# svf.net
KiCad netlist of a schematic drawn in EAGLE
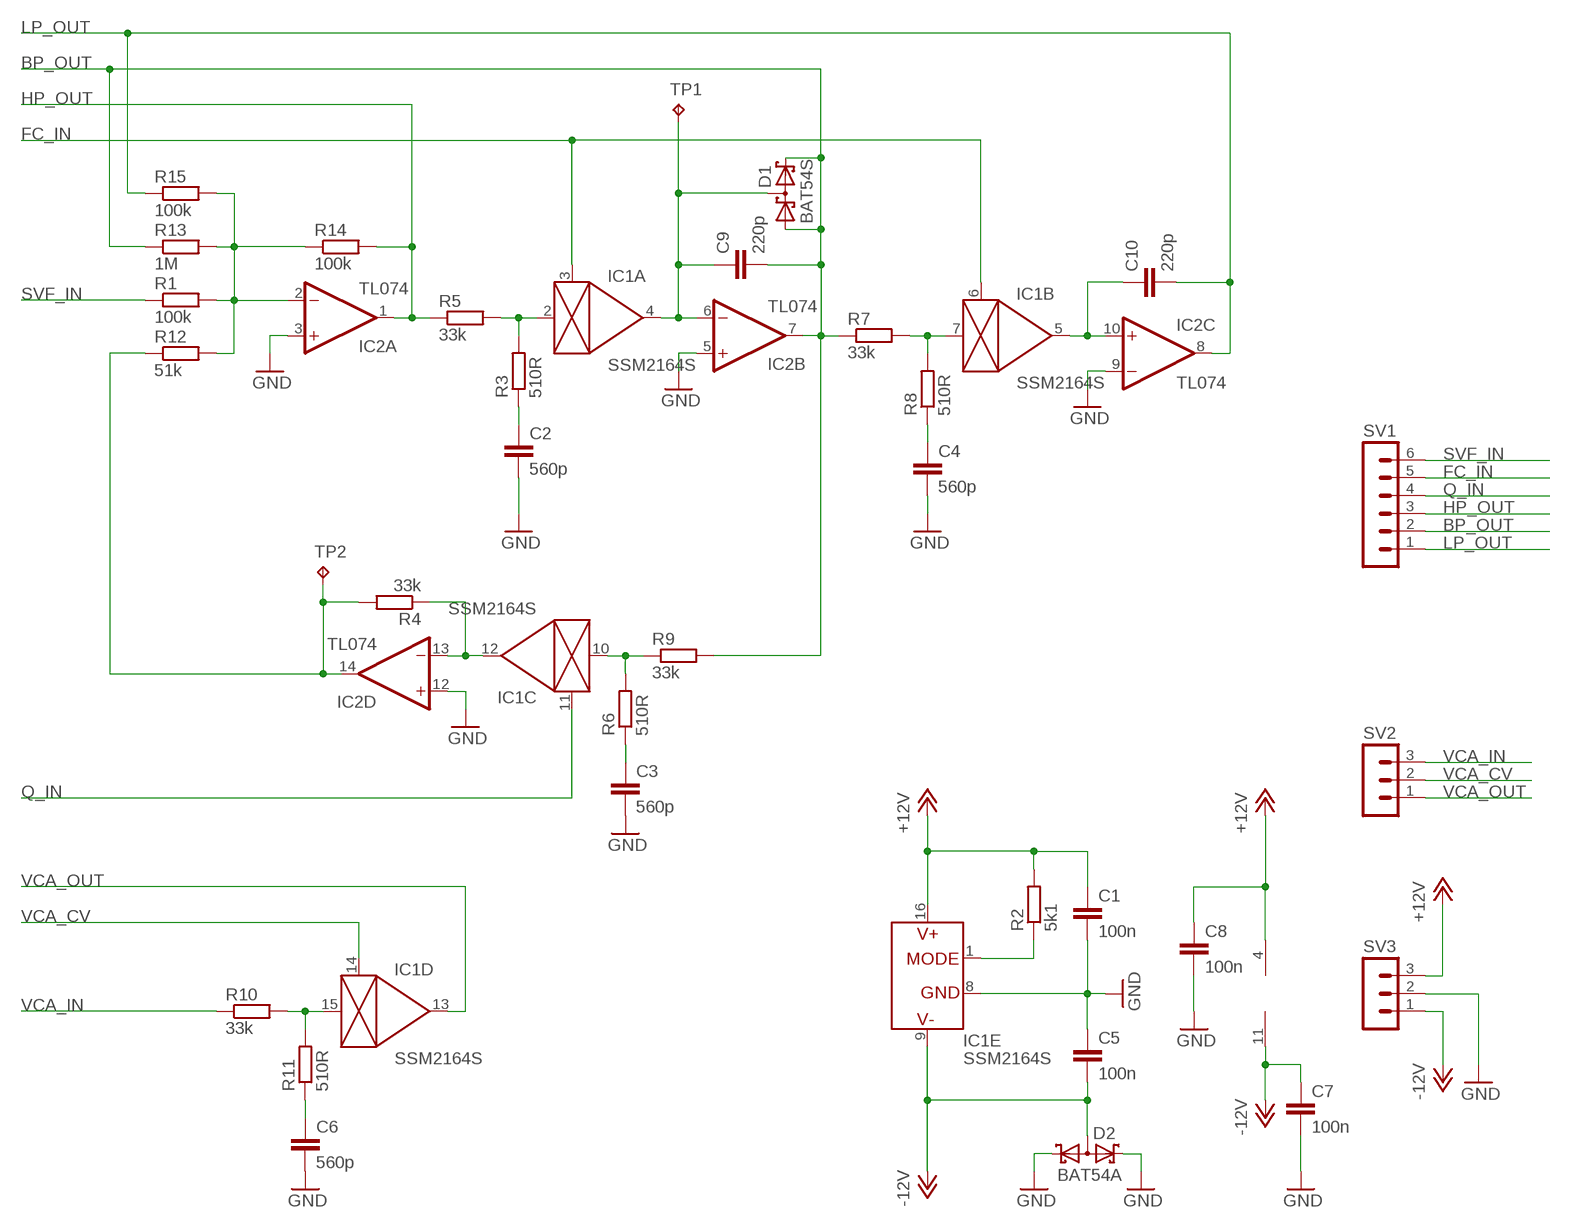
[diagram p0: schematic, sheet 1]

(export (version "E")
  (design (tool "Eeschema 10.0.6"))
  (components
    (comp (ref "C1")
      (value "100n")
      (footprint "eagle-import:C0603")
      (libsource (lib "eagle-import") (part "C-EUC0603"))
    )
    (comp (ref "C2")
      (value "560p")
      (footprint "eagle-import:C0603")
      (libsource (lib "eagle-import") (part "C-EUC0603"))
    )
    (comp (ref "C3")
      (value "560p")
      (footprint "eagle-import:C0603")
      (libsource (lib "eagle-import") (part "C-EUC0603"))
    )
    (comp (ref "C4")
      (value "560p")
      (footprint "eagle-import:C0603")
      (libsource (lib "eagle-import") (part "C-EUC0603"))
    )
    (comp (ref "C5")
      (value "100n")
      (footprint "eagle-import:C0603")
      (libsource (lib "eagle-import") (part "C-EUC0603"))
    )
    (comp (ref "C6")
      (value "560p")
      (footprint "eagle-import:C0603")
      (libsource (lib "eagle-import") (part "C-EUC0603"))
    )
    (comp (ref "C7")
      (value "100n")
      (footprint "eagle-import:C0603")
      (libsource (lib "eagle-import") (part "C-EUC0603"))
    )
    (comp (ref "C8")
      (value "100n")
      (footprint "eagle-import:C0603")
      (libsource (lib "eagle-import") (part "C-EUC0603"))
    )
    (comp (ref "C9")
      (value "220p")
      (footprint "eagle-import:C0603")
      (libsource (lib "eagle-import") (part "C-EUC0603"))
    )
    (comp (ref "C10")
      (value "220p")
      (footprint "eagle-import:C0603")
      (libsource (lib "eagle-import") (part "C-EUC0603"))
    )
    (comp (ref "D1")
      (value "BAT54S")
      (footprint "eagle-import:SOT23")
      (libsource (lib "eagle-import") (part "BAT54S"))
    )
    (comp (ref "D2")
      (value "BAT54A")
      (footprint "eagle-import:SOT23")
      (libsource (lib "eagle-import") (part "BAT54A"))
    )
    (comp (ref "IC1")
      (value "SSM2164S")
      (footprint "eagle-import:SOIC16N")
      (libsource (lib "eagle-import") (part "SSM2164S"))
    )
    (comp (ref "IC2")
      (value "TL074")
      (footprint "eagle-import:SO14")
      (libsource (lib "eagle-import") (part "TL074D"))
    )
    (comp (ref "R1")
      (value "100k")
      (footprint "eagle-import:0603")
      (libsource (lib "eagle-import") (part "R-EU_0603"))
    )
    (comp (ref "R2")
      (value "5k1")
      (footprint "eagle-import:0603")
      (libsource (lib "eagle-import") (part "R-EU_0603"))
    )
    (comp (ref "R3")
      (value "510R")
      (footprint "eagle-import:0603")
      (libsource (lib "eagle-import") (part "R-EU_0603"))
    )
    (comp (ref "R4")
      (value "33k")
      (footprint "eagle-import:0603")
      (libsource (lib "eagle-import") (part "R-EU_0603"))
    )
    (comp (ref "R5")
      (value "33k")
      (footprint "eagle-import:0603")
      (libsource (lib "eagle-import") (part "R-EU_0603"))
    )
    (comp (ref "R6")
      (value "510R")
      (footprint "eagle-import:0603")
      (libsource (lib "eagle-import") (part "R-EU_0603"))
    )
    (comp (ref "R7")
      (value "33k")
      (footprint "eagle-import:0603")
      (libsource (lib "eagle-import") (part "R-EU_0603"))
    )
    (comp (ref "R8")
      (value "510R")
      (footprint "eagle-import:0603")
      (libsource (lib "eagle-import") (part "R-EU_0603"))
    )
    (comp (ref "R9")
      (value "33k")
      (footprint "eagle-import:0603")
      (libsource (lib "eagle-import") (part "R-EU_0603"))
    )
    (comp (ref "R10")
      (value "33k")
      (footprint "eagle-import:0603")
      (libsource (lib "eagle-import") (part "R-EU_0603"))
    )
    (comp (ref "R11")
      (value "510R")
      (footprint "eagle-import:0603")
      (libsource (lib "eagle-import") (part "R-EU_0603"))
    )
    (comp (ref "R12")
      (value "51k")
      (footprint "eagle-import:0603")
      (libsource (lib "eagle-import") (part "R-EU_0603"))
    )
    (comp (ref "R13")
      (value "1M")
      (footprint "eagle-import:0603")
      (libsource (lib "eagle-import") (part "R-EU_0603"))
    )
    (comp (ref "R14")
      (value "100k")
      (footprint "eagle-import:0603")
      (libsource (lib "eagle-import") (part "R-EU_0603"))
    )
    (comp (ref "R15")
      (value "100k")
      (footprint "eagle-import:0603")
      (libsource (lib "eagle-import") (part "R-EU_0603"))
    )
    (comp (ref "SV1")
      (value "MA06-1")
      (footprint "eagle-import:MA06-1")
      (libsource (lib "eagle-import") (part "MA06-1"))
    )
    (comp (ref "SV2")
      (value "MA03-1")
      (footprint "eagle-import:MA03-1")
      (libsource (lib "eagle-import") (part "MA03-1"))
    )
    (comp (ref "SV3")
      (value "MA03-1")
      (footprint "eagle-import:MA03-1")
      (libsource (lib "eagle-import") (part "MA03-1"))
    )
    (comp (ref "TP1")
      (value "TPPAD1-13")
      (footprint "eagle-import:P1-13")
      (libsource (lib "eagle-import") (part "TPPAD1-13"))
    )
    (comp (ref "TP2")
      (value "TPPAD1-13")
      (footprint "eagle-import:P1-13")
      (libsource (lib "eagle-import") (part "TPPAD1-13"))
    )
  )
  (nets
    (net (code "1") (name "+12V") (class "Default")
      (node (ref "C1") (pin "1") (pinfunction "1_1") (pintype "passive"))
      (node (ref "C8") (pin "1") (pinfunction "1_1") (pintype "passive"))
      (node (ref "IC1") (pin "16") (pinfunction "V+_16") (pintype "power_in"))
      (node (ref "IC2") (pin "4") (pinfunction "V+_4") (pintype "power_in"))
      (node (ref "R2") (pin "2") (pinfunction "2_2") (pintype "passive"))
      (node (ref "SV3") (pin "3") (pinfunction "3_3") (pintype "passive"))
    )
    (net (code "2") (name "-12V") (class "Default")
      (node (ref "C5") (pin "2") (pinfunction "2_2") (pintype "passive"))
      (node (ref "C7") (pin "1") (pinfunction "1_1") (pintype "passive"))
      (node (ref "D2") (pin "3") (pinfunction "AA_3") (pintype "passive"))
      (node (ref "IC1") (pin "9") (pinfunction "V-_9") (pintype "power_in"))
      (node (ref "IC2") (pin "11") (pinfunction "V-_11") (pintype "power_in"))
      (node (ref "SV3") (pin "1") (pinfunction "1_1") (pintype "passive"))
    )
    (net (code "3") (name "/BP_OUT") (class "Default")
      (node (ref "C9") (pin "2") (pinfunction "2_2") (pintype "passive"))
      (node (ref "D1") (pin "1") (pinfunction "A1_1") (pintype "passive"))
      (node (ref "D1") (pin "2") (pinfunction "C2_2") (pintype "passive"))
      (node (ref "IC2") (pin "7") (pinfunction "OUT_7") (pintype "output"))
      (node (ref "R13") (pin "1") (pinfunction "1_1") (pintype "passive"))
      (node (ref "R7") (pin "1") (pinfunction "1_1") (pintype "passive"))
      (node (ref "R9") (pin "2") (pinfunction "2_2") (pintype "passive"))
      (node (ref "SV1") (pin "2") (pinfunction "2_2") (pintype "passive"))
    )
    (net (code "4") (name "/FC_IN") (class "Default")
      (node (ref "IC1") (pin "3") (pinfunction "CTRL_3") (pintype "input"))
      (node (ref "IC1") (pin "6") (pinfunction "CTRL_6") (pintype "input"))
      (node (ref "SV1") (pin "5") (pinfunction "5_5") (pintype "passive"))
    )
    (net (code "5") (name "/HP_OUT") (class "Default")
      (node (ref "IC2") (pin "1") (pinfunction "OUT_1") (pintype "output"))
      (node (ref "R14") (pin "2") (pinfunction "2_2") (pintype "passive"))
      (node (ref "R5") (pin "1") (pinfunction "1_1") (pintype "passive"))
      (node (ref "SV1") (pin "3") (pinfunction "3_3") (pintype "passive"))
    )
    (net (code "6") (name "/LP_OUT") (class "Default")
      (node (ref "C10") (pin "2") (pinfunction "2_2") (pintype "passive"))
      (node (ref "IC2") (pin "8") (pinfunction "OUT_8") (pintype "output"))
      (node (ref "R15") (pin "1") (pinfunction "1_1") (pintype "passive"))
      (node (ref "SV1") (pin "1") (pinfunction "1_1") (pintype "passive"))
    )
    (net (code "7") (name "/Q_IN") (class "Default")
      (node (ref "IC1") (pin "11") (pinfunction "CTRL_11") (pintype "input"))
      (node (ref "SV1") (pin "4") (pinfunction "4_4") (pintype "passive"))
    )
    (net (code "8") (name "/SVF_IN") (class "Default")
      (node (ref "R1") (pin "1") (pinfunction "1_1") (pintype "passive"))
      (node (ref "SV1") (pin "6") (pinfunction "6_6") (pintype "passive"))
    )
    (net (code "9") (name "/VCA_CV") (class "Default")
      (node (ref "IC1") (pin "14") (pinfunction "CTRL_14") (pintype "input"))
      (node (ref "SV2") (pin "2") (pinfunction "2_2") (pintype "passive"))
    )
    (net (code "10") (name "/VCA_IN") (class "Default")
      (node (ref "R10") (pin "1") (pinfunction "1_1") (pintype "passive"))
      (node (ref "SV2") (pin "3") (pinfunction "3_3") (pintype "passive"))
    )
    (net (code "11") (name "/VCA_OUT") (class "Default")
      (node (ref "IC1") (pin "13") (pinfunction "OUT_13") (pintype "output"))
      (node (ref "SV2") (pin "1") (pinfunction "1_1") (pintype "passive"))
    )
    (net (code "12") (name "GND") (class "Default")
      (node (ref "C1") (pin "2") (pinfunction "2_2") (pintype "passive"))
      (node (ref "C2") (pin "2") (pinfunction "2_2") (pintype "passive"))
      (node (ref "C3") (pin "2") (pinfunction "2_2") (pintype "passive"))
      (node (ref "C4") (pin "2") (pinfunction "2_2") (pintype "passive"))
      (node (ref "C5") (pin "1") (pinfunction "1_1") (pintype "passive"))
      (node (ref "C6") (pin "2") (pinfunction "2_2") (pintype "passive"))
      (node (ref "C7") (pin "2") (pinfunction "2_2") (pintype "passive"))
      (node (ref "C8") (pin "2") (pinfunction "2_2") (pintype "passive"))
      (node (ref "D2") (pin "1") (pinfunction "K1_1") (pintype "passive"))
      (node (ref "D2") (pin "2") (pinfunction "K2_2") (pintype "passive"))
      (node (ref "IC1") (pin "8") (pinfunction "GND_8") (pintype "power_in"))
      (node (ref "IC2") (pin "12") (pinfunction "+IN_12") (pintype "input"))
      (node (ref "IC2") (pin "3") (pinfunction "+IN_3") (pintype "input"))
      (node (ref "IC2") (pin "5") (pinfunction "+IN_5") (pintype "input"))
      (node (ref "IC2") (pin "9") (pinfunction "-IN_9") (pintype "input"))
      (node (ref "SV3") (pin "2") (pinfunction "2_2") (pintype "passive"))
    )
    (net (code "13") (name "Net-(C2-Pad1)") (class "Default")
      (node (ref "C2") (pin "1") (pinfunction "1_1") (pintype "passive"))
      (node (ref "R3") (pin "1") (pinfunction "1_1") (pintype "passive"))
    )
    (net (code "14") (name "Net-(C3-Pad1)") (class "Default")
      (node (ref "C3") (pin "1") (pinfunction "1_1") (pintype "passive"))
      (node (ref "R6") (pin "1") (pinfunction "1_1") (pintype "passive"))
    )
    (net (code "15") (name "Net-(C4-Pad1)") (class "Default")
      (node (ref "C4") (pin "1") (pinfunction "1_1") (pintype "passive"))
      (node (ref "R8") (pin "1") (pinfunction "1_1") (pintype "passive"))
    )
    (net (code "16") (name "Net-(C6-Pad1)") (class "Default")
      (node (ref "C6") (pin "1") (pinfunction "1_1") (pintype "passive"))
      (node (ref "R11") (pin "1") (pinfunction "1_1") (pintype "passive"))
    )
    (net (code "17") (name "Net-(D1-C1A2)") (class "Default")
      (node (ref "C9") (pin "1") (pinfunction "1_1") (pintype "passive"))
      (node (ref "D1") (pin "3") (pinfunction "C1A2_3") (pintype "passive"))
      (node (ref "IC1") (pin "4") (pinfunction "OUT_4") (pintype "output"))
      (node (ref "IC2") (pin "6") (pinfunction "-IN_6") (pintype "input"))
      (node (ref "TP1") (pin "TP") (pinfunction "TP_TP") (pintype "input"))
    )
    (net (code "18") (name "Net-(IC1A-IN)") (class "Default")
      (node (ref "IC1") (pin "2") (pinfunction "IN_2") (pintype "input"))
      (node (ref "R3") (pin "2") (pinfunction "2_2") (pintype "passive"))
      (node (ref "R5") (pin "2") (pinfunction "2_2") (pintype "passive"))
    )
    (net (code "19") (name "Net-(IC1B-IN)") (class "Default")
      (node (ref "IC1") (pin "7") (pinfunction "IN_7") (pintype "input"))
      (node (ref "R7") (pin "2") (pinfunction "2_2") (pintype "passive"))
      (node (ref "R8") (pin "2") (pinfunction "2_2") (pintype "passive"))
    )
    (net (code "20") (name "Net-(IC1B-OUT)") (class "Default")
      (node (ref "C10") (pin "1") (pinfunction "1_1") (pintype "passive"))
      (node (ref "IC1") (pin "5") (pinfunction "OUT_5") (pintype "output"))
      (node (ref "IC2") (pin "10") (pinfunction "+IN_10") (pintype "input"))
    )
    (net (code "21") (name "Net-(IC1C-IN)") (class "Default")
      (node (ref "IC1") (pin "10") (pinfunction "IN_10") (pintype "input"))
      (node (ref "R6") (pin "2") (pinfunction "2_2") (pintype "passive"))
      (node (ref "R9") (pin "1") (pinfunction "1_1") (pintype "passive"))
    )
    (net (code "22") (name "Net-(IC1C-OUT)") (class "Default")
      (node (ref "IC1") (pin "12") (pinfunction "OUT_12") (pintype "output"))
      (node (ref "IC2") (pin "13") (pinfunction "-IN_13") (pintype "input"))
      (node (ref "R4") (pin "1") (pinfunction "1_1") (pintype "passive"))
    )
    (net (code "23") (name "Net-(IC1D-IN)") (class "Default")
      (node (ref "IC1") (pin "15") (pinfunction "IN_15") (pintype "input"))
      (node (ref "R10") (pin "2") (pinfunction "2_2") (pintype "passive"))
      (node (ref "R11") (pin "2") (pinfunction "2_2") (pintype "passive"))
    )
    (net (code "24") (name "Net-(IC1E-MODE)") (class "Default")
      (node (ref "IC1") (pin "1") (pinfunction "MODE_1") (pintype "input"))
      (node (ref "R2") (pin "1") (pinfunction "1_1") (pintype "passive"))
    )
    (net (code "25") (name "Net-(IC2A--IN)") (class "Default")
      (node (ref "IC2") (pin "2") (pinfunction "-IN_2") (pintype "input"))
      (node (ref "R1") (pin "2") (pinfunction "2_2") (pintype "passive"))
      (node (ref "R12") (pin "2") (pinfunction "2_2") (pintype "passive"))
      (node (ref "R13") (pin "2") (pinfunction "2_2") (pintype "passive"))
      (node (ref "R14") (pin "1") (pinfunction "1_1") (pintype "passive"))
      (node (ref "R15") (pin "2") (pinfunction "2_2") (pintype "passive"))
    )
    (net (code "26") (name "Net-(IC2D-OUT)") (class "Default")
      (node (ref "IC2") (pin "14") (pinfunction "OUT_14") (pintype "output"))
      (node (ref "R12") (pin "1") (pinfunction "1_1") (pintype "passive"))
      (node (ref "R4") (pin "2") (pinfunction "2_2") (pintype "passive"))
      (node (ref "TP2") (pin "TP") (pinfunction "TP_TP") (pintype "input"))
    )
  )
)
